# SCH_Embedded_Watch_2023-10-30.net
KiCad netlist of a schematic drawn in EasyEDA
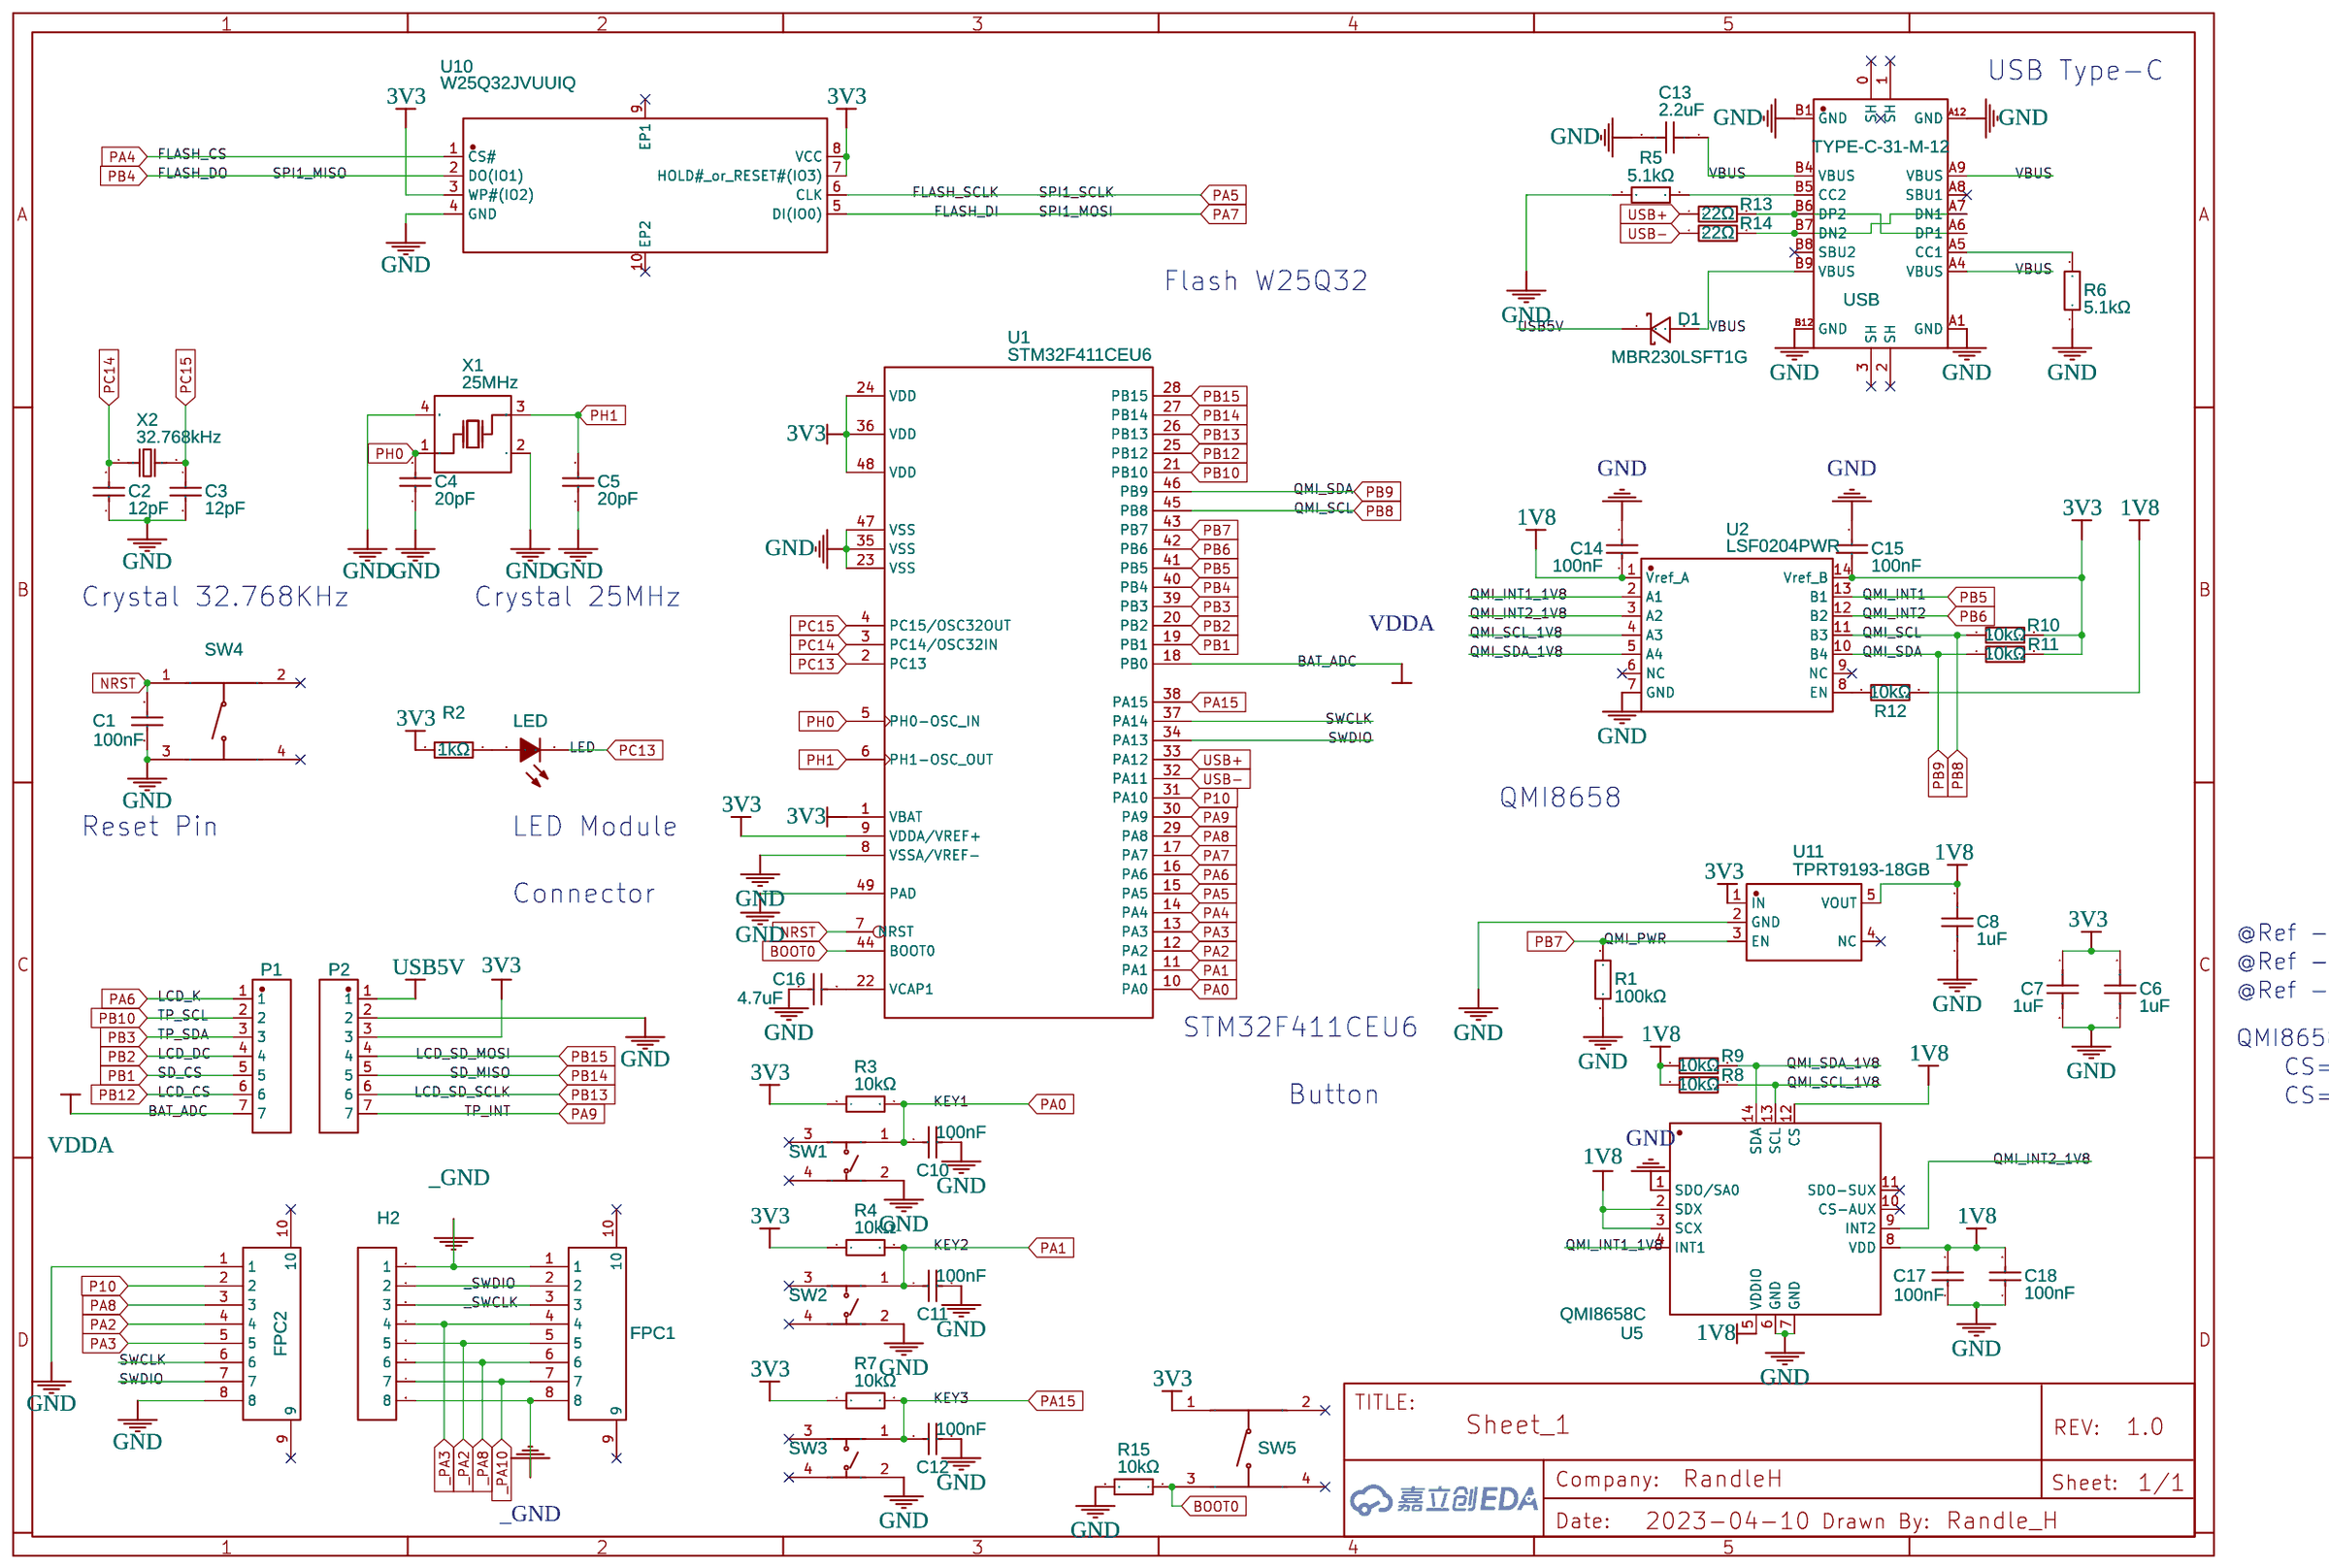
[diagram p0: schematic sheet]

(export (version "E")
  (design (tool "Eeschema 10.0.6"))
  (components
    (comp (ref "C1")
      (value "100nF")
      (fields
        (field (name "Manufacturer Part") "CL05B104KO5NNNC")
        (field (name "Manufacturer") "SAMSUNG(三星)")
      )
      (libsource (lib "") (part "CL05B104KO5NNNC"))
    )
    (comp (ref "C2")
      (value "12pF")
      (fields (field (name "Manufacturer Part") "0402CG120J500NT") (field (name "Manufacturer") "FH(风华)"))
      (libsource (lib "") (part "0402CG120J500NT_1"))
    )
    (comp (ref "C3")
      (value "12pF")
      (fields (field (name "Manufacturer Part") "0402CG120J500NT") (field (name "Manufacturer") "FH(风华)"))
      (libsource (lib "") (part "0402CG120J500NT"))
    )
    (comp (ref "C4")
      (value "20pF")
      (fields (field (name "Manufacturer Part") "0402CG200J500NT") (field (name "Manufacturer") "FH(风华)"))
      (libsource (lib "") (part "0402CG200J500NT"))
    )
    (comp (ref "C5")
      (value "20pF")
      (fields (field (name "Manufacturer Part") "0402CG200J500NT") (field (name "Manufacturer") "FH(风华)"))
      (libsource (lib "") (part "0402CG200J500NT"))
    )
    (comp (ref "C6")
      (value "1uF")
      (fields
        (field (name "Manufacturer Part") "CL05A105KA5NQNC")
        (field (name "Manufacturer") "SAMSUNG(三星)")
      )
      (libsource (lib "") (part "CL05A105KA5NQNC"))
    )
    (comp (ref "C7")
      (value "1uF")
      (fields
        (field (name "Manufacturer Part") "CL05A105KA5NQNC")
        (field (name "Manufacturer") "SAMSUNG(三星)")
      )
      (libsource (lib "") (part "CL05A105KA5NQNC_1"))
    )
    (comp (ref "C8")
      (value "1uF")
      (fields
        (field (name "Manufacturer Part") "CL05A105KA5NQNC")
        (field (name "Manufacturer") "SAMSUNG(三星)")
      )
      (libsource (lib "") (part "CL05A105KA5NQNC"))
    )
    (comp (ref "C10")
      (value "100nF")
      (fields
        (field (name "Manufacturer Part") "CL05B104KO5NNNC")
        (field (name "Manufacturer") "SAMSUNG(三星)")
      )
      (libsource (lib "") (part "CL05B104KO5NNNC_2"))
    )
    (comp (ref "C11")
      (value "100nF")
      (fields
        (field (name "Manufacturer Part") "CL05B104KO5NNNC")
        (field (name "Manufacturer") "SAMSUNG(三星)")
      )
      (libsource (lib "") (part "CL05B104KO5NNNC_2"))
    )
    (comp (ref "C12")
      (value "100nF")
      (fields
        (field (name "Manufacturer Part") "CL05B104KO5NNNC")
        (field (name "Manufacturer") "SAMSUNG(三星)")
      )
      (libsource (lib "") (part "CL05B104KO5NNNC_2"))
    )
    (comp (ref "C13")
      (value "2.2uF")
      (fields
        (field (name "Manufacturer Part") "CL21A225KBQNNNE")
        (field (name "Manufacturer") "SAMSUNG(三星)")
      )
      (libsource (lib "") (part "CL21A225KBQNNNE"))
    )
    (comp (ref "C14")
      (value "100nF")
      (fields
        (field (name "Manufacturer Part") "CL05B104KO5NNNC")
        (field (name "Manufacturer") "SAMSUNG(三星)")
      )
      (libsource (lib "") (part "CL05B104KO5NNNC_3"))
    )
    (comp (ref "C15")
      (value "100nF")
      (fields
        (field (name "Manufacturer Part") "CL05B104KO5NNNC")
        (field (name "Manufacturer") "SAMSUNG(三星)")
      )
      (libsource (lib "") (part "CL05B104KO5NNNC_1"))
    )
    (comp (ref "C16")
      (value "4.7uF")
      (fields
        (field (name "Manufacturer Part") "CL05A475MP5NRNC")
        (field (name "Manufacturer") "SAMSUNG(三星)")
      )
      (libsource (lib "") (part "CL05A475MP5NRNC"))
    )
    (comp (ref "C17")
      (value "100nF")
      (fields
        (field (name "Manufacturer Part") "CL05B104KO5NNNC")
        (field (name "Manufacturer") "SAMSUNG(三星)")
      )
      (libsource (lib "") (part "CL05B104KO5NNNC"))
    )
    (comp (ref "C18")
      (value "100nF")
      (fields
        (field (name "Manufacturer Part") "CL05B104KO5NNNC")
        (field (name "Manufacturer") "SAMSUNG(三星)")
      )
      (libsource (lib "") (part "CL05B104KO5NNNC_1"))
    )
    (comp (ref "D1")
      (value "MBR230LSFT1G")
      (fields (field (name "Manufacturer") "onsemi(安森美)"))
      (libsource (lib "") (part "MBR230LSFT1G"))
    )
    (comp (ref "FPC1")
      (value "C2883764")
      (fields (field (name "Manufacturer Part") "AFC01-S08FCA-00") (field (name "Manufacturer") "JS(钜硕电子)"))
      (libsource (lib "") (part "AFC01-S08FCA-00"))
    )
    (comp (ref "FPC2")
      (value "C2883764")
      (fields (field (name "Manufacturer Part") "AFC01-S08FCA-00") (field (name "Manufacturer") "JS(钜硕电子)"))
      (libsource (lib "") (part "AFC01-S08FCA-00"))
    )
    (comp (ref "H2") (value "HDR-F-2.54_1x8") (libsource (lib "") (part "HDR-F-2.54_1x8")))
    (comp (ref "LED")
      (value "19-213/Y2C-CQ2R2L/3T(CY)")
      (fields (field (name "Manufacturer") "EVERLIGHT(亿光)"))
      (libsource (lib "") (part "19-213/Y2C-CQ2R2L/3T(CY)"))
    )
    (comp (ref "P1")
      (value "PM2.54-1*7")
      (fields
        (field (name "Manufacturer Part") "X6511WVS-07H-C60D48R1")
        (field (name "Manufacturer") "XKB Connectivity(中国星坤)")
      )
      (libsource (lib "") (part "PM2.54-1*7_1"))
    )
    (comp (ref "P2")
      (value "PM2.54-1*7")
      (fields
        (field (name "Manufacturer Part") "X6511WVS-07H-C60D48R1")
        (field (name "Manufacturer") "XKB Connectivity(中国星坤)")
      )
      (libsource (lib "") (part "PM2.54-1*7"))
    )
    (comp (ref "R1")
      (value "100kΩ")
      (fields
        (field (name "Manufacturer Part") "0402WGF1003TCE")
        (field (name "Manufacturer") "UNI-ROYAL(厚声)")
      )
      (libsource (lib "") (part "0402WGF1003TCE"))
    )
    (comp (ref "R2")
      (value "1kΩ")
      (fields
        (field (name "Manufacturer Part") "0402WGF1001TCE")
        (field (name "Manufacturer") "UNI-ROYAL(厚声)")
      )
      (libsource (lib "") (part "0402WGF1001TCE"))
    )
    (comp (ref "R3")
      (value "10kΩ")
      (fields
        (field (name "Manufacturer Part") "0402WGF1002TCE")
        (field (name "Manufacturer") "UNI-ROYAL(厚声)")
      )
      (libsource (lib "") (part "0402WGF1002TCE"))
    )
    (comp (ref "R4")
      (value "10kΩ")
      (fields
        (field (name "Manufacturer Part") "0402WGF1002TCE")
        (field (name "Manufacturer") "UNI-ROYAL(厚声)")
      )
      (libsource (lib "") (part "0402WGF1002TCE"))
    )
    (comp (ref "R5")
      (value "5.1kΩ")
      (fields
        (field (name "Manufacturer Part") "0402WGF5101TCE")
        (field (name "Manufacturer") "UNI-ROYAL(厚声)")
      )
      (libsource (lib "") (part "0402WGF5101TCE_1"))
    )
    (comp (ref "R6")
      (value "5.1kΩ")
      (fields
        (field (name "Manufacturer Part") "0402WGF5101TCE")
        (field (name "Manufacturer") "UNI-ROYAL(厚声)")
      )
      (libsource (lib "") (part "0402WGF5101TCE"))
    )
    (comp (ref "R7")
      (value "10kΩ")
      (fields
        (field (name "Manufacturer Part") "0402WGF1002TCE")
        (field (name "Manufacturer") "UNI-ROYAL(厚声)")
      )
      (libsource (lib "") (part "0402WGF1002TCE"))
    )
    (comp (ref "R8")
      (value "10kΩ")
      (fields
        (field (name "Manufacturer Part") "0402WGF1002TCE")
        (field (name "Manufacturer") "UNI-ROYAL(厚声)")
      )
      (libsource (lib "") (part "0402WGF1002TCE"))
    )
    (comp (ref "R9")
      (value "10kΩ")
      (fields
        (field (name "Manufacturer Part") "0402WGF1002TCE")
        (field (name "Manufacturer") "UNI-ROYAL(厚声)")
      )
      (libsource (lib "") (part "0402WGF1002TCE"))
    )
    (comp (ref "R10")
      (value "10kΩ")
      (fields
        (field (name "Manufacturer Part") "0402WGF1002TCE")
        (field (name "Manufacturer") "UNI-ROYAL(厚声)")
      )
      (libsource (lib "") (part "0402WGF1002TCE"))
    )
    (comp (ref "R11")
      (value "10kΩ")
      (fields
        (field (name "Manufacturer Part") "0402WGF1002TCE")
        (field (name "Manufacturer") "UNI-ROYAL(厚声)")
      )
      (libsource (lib "") (part "0402WGF1002TCE"))
    )
    (comp (ref "R12")
      (value "10kΩ")
      (fields
        (field (name "Manufacturer Part") "0402WGF1002TCE")
        (field (name "Manufacturer") "UNI-ROYAL(厚声)")
      )
      (libsource (lib "") (part "0402WGF1002TCE"))
    )
    (comp (ref "R13")
      (value "22Ω")
      (fields
        (field (name "Manufacturer Part") "0402WGF220JTCE")
        (field (name "Manufacturer") "UNI-ROYAL(厚声)")
      )
      (libsource (lib "") (part "0402WGF220JTCE"))
    )
    (comp (ref "R14")
      (value "22Ω")
      (fields
        (field (name "Manufacturer Part") "0402WGF220JTCE")
        (field (name "Manufacturer") "UNI-ROYAL(厚声)")
      )
      (libsource (lib "") (part "0402WGF220JTCE"))
    )
    (comp (ref "R15")
      (value "10kΩ")
      (fields
        (field (name "Manufacturer Part") "0402WGF1002TCE")
        (field (name "Manufacturer") "UNI-ROYAL(厚声)")
      )
      (libsource (lib "") (part "0402WGF1002TCE_1"))
    )
    (comp (ref "SW1")
      (value "EVQPUD02K")
      (fields (field (name "Manufacturer") "PANASONIC(松下)"))
      (libsource (lib "") (part "EVQPUD02K"))
    )
    (comp (ref "SW2")
      (value "EVQPUD02K")
      (fields (field (name "Manufacturer") "PANASONIC(松下)"))
      (libsource (lib "") (part "EVQPUD02K"))
    )
    (comp (ref "SW3")
      (value "EVQPUD02K")
      (fields (field (name "Manufacturer") "PANASONIC(松下)"))
      (libsource (lib "") (part "EVQPUD02K"))
    )
    (comp (ref "SW4")
      (value "PTS830GM140SMTRLFS")
      (fields (field (name "Manufacturer") "C&K"))
      (libsource (lib "") (part "PTS830GM140SMTRLFS"))
    )
    (comp (ref "SW5")
      (value "PTS830GM140SMTRLFS")
      (fields (field (name "Manufacturer") "C&K"))
      (libsource (lib "") (part "PTS830GM140SMTRLFS"))
    )
    (comp (ref "U1")
      (value "STM32F411CEU6")
      (fields (field (name "Manufacturer") "ST(意法半导体)"))
      (libsource (lib "") (part "STM32F411CEU6"))
    )
    (comp (ref "U2")
      (value "LSF0204PWR")
      (fields (field (name "Manufacturer") "TI(德州仪器)"))
      (libsource (lib "") (part "LSF0204PWR"))
    )
    (comp (ref "U5")
      (value "QMI8658C")
      (fields (field (name "Manufacturer") "QST(上海矽睿)"))
      (libsource (lib "") (part "QMI8658C"))
    )
    (comp (ref "U10")
      (value "W25Q32JVUUIQ")
      (fields (field (name "Manufacturer") "WINBOND(华邦)"))
      (libsource (lib "") (part "W25Q32JVUUIQ"))
    )
    (comp (ref "U11")
      (value "TPRT9193-18GB")
      (fields (field (name "Manufacturer") "TECH PUBLIC(台舟)"))
      (libsource (lib "") (part "TPRT9193-18GB"))
    )
    (comp (ref "USB")
      (value "TYPE-C-31-M-12")
      (fields (field (name "Manufacturer") "韩国韩荣"))
      (libsource (lib "") (part "TYPE-C-31-M-12"))
    )
    (comp (ref "X1")
      (value "25MHz")
      (fields (field (name "Manufacturer Part") "TAXM25M4RLBCCT2T") (field (name "Manufacturer") "TAE(雅晶鑫)"))
      (libsource (lib "") (part "SMD-3225_4P25MHZ20PF10PPM-40&#126;+85℃"))
    )
    (comp (ref "X2")
      (value "32.768kHz")
      (fields (field (name "Manufacturer Part") "Q13FC1350000400") (field (name "Manufacturer") "EPSON(爱普生)"))
      (libsource (lib "") (part "Q13FC1350000400"))
    )
  )
  (nets
    (net (code "1") (name "/QMI_INT1_1V8") (class "Default")
      (node (ref "U2") (pin "2") (pinfunction "A1_2") (pintype "unspecified"))
      (node (ref "U5") (pin "4") (pinfunction "INT1_4") (pintype "unspecified"))
    )
    (net (code "2") (name "/QMI_INT2_1V8") (class "Default")
      (node (ref "U2") (pin "3") (pinfunction "A2_3") (pintype "unspecified"))
      (node (ref "U5") (pin "9") (pinfunction "INT2_9") (pintype "unspecified"))
    )
    (net (code "3") (name "/QMI_SCL_1V8") (class "Default")
      (node (ref "R8") (pin "2") (pinfunction "2_2") (pintype "input"))
      (node (ref "U2") (pin "4") (pinfunction "A3_4") (pintype "unspecified"))
      (node (ref "U5") (pin "13") (pinfunction "SCL_13") (pintype "unspecified"))
    )
    (net (code "4") (name "/QMI_SDA_1V8") (class "Default")
      (node (ref "R9") (pin "2") (pinfunction "2_2") (pintype "input"))
      (node (ref "U2") (pin "5") (pinfunction "A4_5") (pintype "unspecified"))
      (node (ref "U5") (pin "14") (pinfunction "SDA_14") (pintype "unspecified"))
    )
    (net (code "5") (name "/SWCLK") (class "Default")
      (node (ref "FPC2") (pin "6") (pinfunction "6_6") (pintype "unspecified"))
      (node (ref "U1") (pin "37") (pinfunction "PA14_37") (pintype "unspecified"))
    )
    (net (code "6") (name "/SWDIO") (class "Default")
      (node (ref "FPC2") (pin "7") (pinfunction "7_7") (pintype "unspecified"))
      (node (ref "U1") (pin "34") (pinfunction "PA13_34") (pintype "unspecified"))
    )
    (net (code "7") (name "/VBUS") (class "Default")
      (node (ref "C13") (pin "1") (pinfunction "1_1") (pintype "unspecified"))
      (node (ref "D1") (pin "2") (pinfunction "A_2") (pintype "unspecified"))
      (node (ref "USB") (pin "A4") (pinfunction "VBUS_A4") (pintype "unspecified"))
      (node (ref "USB") (pin "A9") (pinfunction "VBUS_A9") (pintype "unspecified"))
      (node (ref "USB") (pin "B4") (pinfunction "VBUS_B4") (pintype "unspecified"))
      (node (ref "USB") (pin "B9") (pinfunction "VBUS_B9") (pintype "unspecified"))
    )
    (net (code "8") (name "/_SWCLK") (class "Default")
      (node (ref "FPC1") (pin "3") (pinfunction "3_3") (pintype "unspecified"))
      (node (ref "H2") (pin "3") (pinfunction "3_3") (pintype "unspecified"))
    )
    (net (code "9") (name "/_SWDIO") (class "Default")
      (node (ref "FPC1") (pin "2") (pinfunction "2_2") (pintype "unspecified"))
      (node (ref "H2") (pin "2") (pinfunction "2_2") (pintype "unspecified"))
    )
    (net (code "10") (name "1V8") (class "Default")
      (node (ref "C14") (pin "1") (pinfunction "1_1") (pintype "input"))
      (node (ref "C17") (pin "1") (pinfunction "1_1") (pintype "input"))
      (node (ref "C18") (pin "2") (pinfunction "2_2") (pintype "input"))
      (node (ref "C8") (pin "2") (pinfunction "2_2") (pintype "unspecified"))
      (node (ref "R12") (pin "2") (pinfunction "2_2") (pintype "input"))
      (node (ref "R8") (pin "1") (pinfunction "1_1") (pintype "input"))
      (node (ref "R9") (pin "1") (pinfunction "1_1") (pintype "input"))
      (node (ref "U11") (pin "5") (pinfunction "VOUT_5") (pintype "unspecified"))
      (node (ref "U2") (pin "1") (pinfunction "Vref_A_1") (pintype "unspecified"))
      (node (ref "U5") (pin "12") (pinfunction "CS_12") (pintype "unspecified"))
      (node (ref "U5") (pin "2") (pinfunction "SDX_2") (pintype "unspecified"))
      (node (ref "U5") (pin "3") (pinfunction "SCX_3") (pintype "unspecified"))
      (node (ref "U5") (pin "5") (pinfunction "VDDIO_5") (pintype "unspecified"))
      (node (ref "U5") (pin "8") (pinfunction "VDD_8") (pintype "unspecified"))
    )
    (net (code "11") (name "3V3") (class "Default")
      (node (ref "C15") (pin "1") (pinfunction "1_1") (pintype "input"))
      (node (ref "C6") (pin "2") (pinfunction "2_2") (pintype "unspecified"))
      (node (ref "C7") (pin "1") (pinfunction "1_1") (pintype "unspecified"))
      (node (ref "P2") (pin "3") (pinfunction "3_3") (pintype "unspecified"))
      (node (ref "R10") (pin "2") (pinfunction "2_2") (pintype "input"))
      (node (ref "R11") (pin "2") (pinfunction "2_2") (pintype "input"))
      (node (ref "R2") (pin "1") (pinfunction "1_1") (pintype "input"))
      (node (ref "R3") (pin "1") (pinfunction "1_1") (pintype "input"))
      (node (ref "R4") (pin "1") (pinfunction "1_1") (pintype "input"))
      (node (ref "R7") (pin "1") (pinfunction "1_1") (pintype "input"))
      (node (ref "SW5") (pin "1") (pinfunction "1_1") (pintype "unspecified"))
      (node (ref "U1") (pin "1") (pinfunction "VBAT_1") (pintype "passive"))
      (node (ref "U1") (pin "24") (pinfunction "VDD_24") (pintype "unspecified"))
      (node (ref "U1") (pin "36") (pinfunction "VDD_36") (pintype "unspecified"))
      (node (ref "U1") (pin "48") (pinfunction "VDD_48") (pintype "unspecified"))
      (node (ref "U1") (pin "9") (pinfunction "VDDA/VREF+_9") (pintype "passive"))
      (node (ref "U10") (pin "3") (pinfunction "WP#(IO2)_3") (pintype "unspecified"))
      (node (ref "U10") (pin "7") (pinfunction "HOLD#_or_RESET#(IO3)_7") (pintype "unspecified"))
      (node (ref "U10") (pin "8") (pinfunction "VCC_8") (pintype "unspecified"))
      (node (ref "U11") (pin "1") (pinfunction "IN_1") (pintype "unspecified"))
      (node (ref "U2") (pin "14") (pinfunction "Vref_B_14") (pintype "unspecified"))
    )
    (net (code "12") (name "BOOT0") (class "Default")
      (node (ref "R15") (pin "1") (pinfunction "1_1") (pintype "input"))
      (node (ref "SW5") (pin "3") (pinfunction "3_3") (pintype "unspecified"))
      (node (ref "U1") (pin "44") (pinfunction "BOOT0_44") (pintype "input"))
    )
    (net (code "13") (name "GND") (class "Default")
      (node (ref "C1") (pin "2") (pinfunction "2_2") (pintype "input"))
      (node (ref "C10") (pin "2") (pinfunction "2_2") (pintype "input"))
      (node (ref "C11") (pin "2") (pinfunction "2_2") (pintype "input"))
      (node (ref "C12") (pin "2") (pinfunction "2_2") (pintype "input"))
      (node (ref "C13") (pin "2") (pinfunction "2_2") (pintype "unspecified"))
      (node (ref "C14") (pin "2") (pinfunction "2_2") (pintype "input"))
      (node (ref "C15") (pin "2") (pinfunction "2_2") (pintype "input"))
      (node (ref "C16") (pin "1") (pinfunction "1_1") (pintype "input"))
      (node (ref "C17") (pin "2") (pinfunction "2_2") (pintype "input"))
      (node (ref "C18") (pin "1") (pinfunction "1_1") (pintype "input"))
      (node (ref "C2") (pin "1") (pinfunction "1_1") (pintype "input"))
      (node (ref "C3") (pin "2") (pinfunction "2_2") (pintype "input"))
      (node (ref "C4") (pin "1") (pinfunction "1_1") (pintype "input"))
      (node (ref "C5") (pin "1") (pinfunction "1_1") (pintype "input"))
      (node (ref "C6") (pin "1") (pinfunction "1_1") (pintype "unspecified"))
      (node (ref "C7") (pin "2") (pinfunction "2_2") (pintype "unspecified"))
      (node (ref "C8") (pin "1") (pinfunction "1_1") (pintype "unspecified"))
      (node (ref "FPC2") (pin "1") (pinfunction "1_1") (pintype "unspecified"))
      (node (ref "FPC2") (pin "8") (pinfunction "8_8") (pintype "unspecified"))
      (node (ref "P2") (pin "2") (pinfunction "2_2") (pintype "unspecified"))
      (node (ref "R1") (pin "1") (pinfunction "1_1") (pintype "input"))
      (node (ref "R15") (pin "2") (pinfunction "2_2") (pintype "input"))
      (node (ref "R5") (pin "2") (pinfunction "2_2") (pintype "input"))
      (node (ref "R6") (pin "1") (pinfunction "1_1") (pintype "input"))
      (node (ref "SW1") (pin "2") (pinfunction "2_2") (pintype "unspecified"))
      (node (ref "SW2") (pin "2") (pinfunction "2_2") (pintype "unspecified"))
      (node (ref "SW3") (pin "2") (pinfunction "2_2") (pintype "unspecified"))
      (node (ref "SW4") (pin "3") (pinfunction "3_3") (pintype "unspecified"))
      (node (ref "U1") (pin "23") (pinfunction "VSS_23") (pintype "unspecified"))
      (node (ref "U1") (pin "35") (pinfunction "VSS_35") (pintype "unspecified"))
      (node (ref "U1") (pin "47") (pinfunction "VSS_47") (pintype "unspecified"))
      (node (ref "U1") (pin "49") (pinfunction "PAD_49") (pintype "passive"))
      (node (ref "U1") (pin "8") (pinfunction "VSSA/VREF-_8") (pintype "passive"))
      (node (ref "U10") (pin "4") (pinfunction "GND_4") (pintype "unspecified"))
      (node (ref "U11") (pin "2") (pinfunction "GND_2") (pintype "unspecified"))
      (node (ref "U2") (pin "7") (pinfunction "GND_7") (pintype "unspecified"))
      (node (ref "U5") (pin "1") (pinfunction "SDO/SA0_1") (pintype "unspecified"))
      (node (ref "U5") (pin "6") (pinfunction "GND_6") (pintype "unspecified"))
      (node (ref "U5") (pin "7") (pinfunction "GND_7") (pintype "unspecified"))
      (node (ref "USB") (pin "A1") (pinfunction "GND_A1") (pintype "unspecified"))
      (node (ref "USB") (pin "A12") (pinfunction "GND_A12") (pintype "unspecified"))
      (node (ref "USB") (pin "B1") (pinfunction "GND_B1") (pintype "unspecified"))
      (node (ref "USB") (pin "B12") (pinfunction "GND_B12") (pintype "unspecified"))
      (node (ref "X1") (pin "2") (pinfunction "GND_2") (pintype "unspecified"))
      (node (ref "X1") (pin "4") (pinfunction "GND_4") (pintype "unspecified"))
    )
    (net (code "14") (name "NRST") (class "Default")
      (node (ref "C1") (pin "1") (pinfunction "1_1") (pintype "input"))
      (node (ref "SW4") (pin "1") (pinfunction "1_1") (pintype "unspecified"))
      (node (ref "U1") (pin "7") (pinfunction "NRST_7") (pintype "unspecified"))
    )
    (net (code "15") (name "Net-(LED-A)") (class "Default")
      (node (ref "LED") (pin "2") (pinfunction "A_2") (pintype "input"))
      (node (ref "R2") (pin "2") (pinfunction "2_2") (pintype "input"))
    )
    (net (code "16") (name "Net-(U1-VCAP1)") (class "Default")
      (node (ref "C16") (pin "2") (pinfunction "2_2") (pintype "input"))
      (node (ref "U1") (pin "22") (pinfunction "VCAP1_22") (pintype "passive"))
    )
    (net (code "17") (name "Net-(U2-EN)") (class "Default")
      (node (ref "R12") (pin "1") (pinfunction "1_1") (pintype "input"))
      (node (ref "U2") (pin "8") (pinfunction "EN_8") (pintype "unspecified"))
    )
    (net (code "18") (name "Net-(USB-CC1)") (class "Default")
      (node (ref "R6") (pin "2") (pinfunction "2_2") (pintype "input"))
      (node (ref "USB") (pin "A5") (pinfunction "CC1_A5") (pintype "unspecified"))
    )
    (net (code "19") (name "Net-(USB-CC2)") (class "Default")
      (node (ref "R5") (pin "1") (pinfunction "1_1") (pintype "input"))
      (node (ref "USB") (pin "B5") (pinfunction "CC2_B5") (pintype "unspecified"))
    )
    (net (code "20") (name "Net-(USB-DN1)") (class "Default")
      (node (ref "R14") (pin "2") (pinfunction "2_2") (pintype "input"))
      (node (ref "USB") (pin "A7") (pinfunction "DN1_A7") (pintype "unspecified"))
      (node (ref "USB") (pin "B7") (pinfunction "DN2_B7") (pintype "unspecified"))
    )
    (net (code "21") (name "Net-(USB-DP1)") (class "Default")
      (node (ref "R13") (pin "2") (pinfunction "2_2") (pintype "input"))
      (node (ref "USB") (pin "A6") (pinfunction "DP1_A6") (pintype "unspecified"))
      (node (ref "USB") (pin "B6") (pinfunction "DP2_B6") (pintype "unspecified"))
    )
    (net (code "22") (name "P10") (class "Default")
      (node (ref "FPC2") (pin "2") (pinfunction "2_2") (pintype "unspecified"))
      (node (ref "U1") (pin "31") (pinfunction "PA10_31") (pintype "unspecified"))
    )
    (net (code "23") (name "PA0") (class "Default")
      (node (ref "C10") (pin "1") (pinfunction "1_1") (pintype "input"))
      (node (ref "R3") (pin "2") (pinfunction "2_2") (pintype "input"))
      (node (ref "SW1") (pin "1") (pinfunction "1_1") (pintype "unspecified"))
      (node (ref "U1") (pin "10") (pinfunction "PA0_10") (pintype "unspecified"))
    )
    (net (code "24") (name "PA1") (class "Default")
      (node (ref "C11") (pin "1") (pinfunction "1_1") (pintype "input"))
      (node (ref "R4") (pin "2") (pinfunction "2_2") (pintype "input"))
      (node (ref "SW2") (pin "1") (pinfunction "1_1") (pintype "unspecified"))
      (node (ref "U1") (pin "11") (pinfunction "PA1_11") (pintype "unspecified"))
    )
    (net (code "25") (name "PA2") (class "Default")
      (node (ref "FPC2") (pin "4") (pinfunction "4_4") (pintype "unspecified"))
      (node (ref "U1") (pin "12") (pinfunction "PA2_12") (pintype "unspecified"))
    )
    (net (code "26") (name "PA3") (class "Default")
      (node (ref "FPC2") (pin "5") (pinfunction "5_5") (pintype "unspecified"))
      (node (ref "U1") (pin "13") (pinfunction "PA3_13") (pintype "unspecified"))
    )
    (net (code "27") (name "PA4") (class "Default")
      (node (ref "U1") (pin "14") (pinfunction "PA4_14") (pintype "unspecified"))
      (node (ref "U10") (pin "1") (pinfunction "CS#_1") (pintype "unspecified"))
    )
    (net (code "28") (name "PA5") (class "Default")
      (node (ref "U1") (pin "15") (pinfunction "PA5_15") (pintype "unspecified"))
      (node (ref "U10") (pin "6") (pinfunction "CLK_6") (pintype "unspecified"))
    )
    (net (code "29") (name "PA6") (class "Default")
      (node (ref "P1") (pin "1") (pinfunction "1_1") (pintype "unspecified"))
      (node (ref "U1") (pin "16") (pinfunction "PA6_16") (pintype "unspecified"))
    )
    (net (code "30") (name "PA7") (class "Default")
      (node (ref "U1") (pin "17") (pinfunction "PA7_17") (pintype "unspecified"))
      (node (ref "U10") (pin "5") (pinfunction "DI(IO0)_5") (pintype "unspecified"))
    )
    (net (code "31") (name "PA8") (class "Default")
      (node (ref "FPC2") (pin "3") (pinfunction "3_3") (pintype "unspecified"))
      (node (ref "U1") (pin "29") (pinfunction "PA8_29") (pintype "unspecified"))
    )
    (net (code "32") (name "PA9") (class "Default")
      (node (ref "P2") (pin "7") (pinfunction "7_7") (pintype "unspecified"))
      (node (ref "U1") (pin "30") (pinfunction "PA9_30") (pintype "unspecified"))
    )
    (net (code "33") (name "PA15") (class "Default")
      (node (ref "C12") (pin "1") (pinfunction "1_1") (pintype "input"))
      (node (ref "R7") (pin "2") (pinfunction "2_2") (pintype "input"))
      (node (ref "SW3") (pin "1") (pinfunction "1_1") (pintype "unspecified"))
      (node (ref "U1") (pin "38") (pinfunction "PA15_38") (pintype "unspecified"))
    )
    (net (code "34") (name "PB1") (class "Default")
      (node (ref "P1") (pin "5") (pinfunction "5_5") (pintype "unspecified"))
      (node (ref "U1") (pin "19") (pinfunction "PB1_19") (pintype "unspecified"))
    )
    (net (code "35") (name "PB2") (class "Default")
      (node (ref "P1") (pin "4") (pinfunction "4_4") (pintype "unspecified"))
      (node (ref "U1") (pin "20") (pinfunction "PB2_20") (pintype "unspecified"))
    )
    (net (code "36") (name "PB3") (class "Default")
      (node (ref "P1") (pin "3") (pinfunction "3_3") (pintype "unspecified"))
      (node (ref "U1") (pin "39") (pinfunction "PB3_39") (pintype "unspecified"))
    )
    (net (code "37") (name "PB4") (class "Default")
      (node (ref "U1") (pin "40") (pinfunction "PB4_40") (pintype "unspecified"))
      (node (ref "U10") (pin "2") (pinfunction "DO(IO1)_2") (pintype "unspecified"))
    )
    (net (code "38") (name "PB5") (class "Default")
      (node (ref "U1") (pin "41") (pinfunction "PB5_41") (pintype "unspecified"))
      (node (ref "U2") (pin "13") (pinfunction "B1_13") (pintype "unspecified"))
    )
    (net (code "39") (name "PB6") (class "Default")
      (node (ref "U1") (pin "42") (pinfunction "PB6_42") (pintype "unspecified"))
      (node (ref "U2") (pin "12") (pinfunction "B2_12") (pintype "unspecified"))
    )
    (net (code "40") (name "PB7") (class "Default")
      (node (ref "R1") (pin "2") (pinfunction "2_2") (pintype "input"))
      (node (ref "U1") (pin "43") (pinfunction "PB7_43") (pintype "unspecified"))
      (node (ref "U11") (pin "3") (pinfunction "EN_3") (pintype "unspecified"))
    )
    (net (code "41") (name "PB8") (class "Default")
      (node (ref "R10") (pin "1") (pinfunction "1_1") (pintype "input"))
      (node (ref "U1") (pin "45") (pinfunction "PB8_45") (pintype "unspecified"))
      (node (ref "U2") (pin "11") (pinfunction "B3_11") (pintype "unspecified"))
    )
    (net (code "42") (name "PB9") (class "Default")
      (node (ref "R11") (pin "1") (pinfunction "1_1") (pintype "input"))
      (node (ref "U1") (pin "46") (pinfunction "PB9_46") (pintype "unspecified"))
      (node (ref "U2") (pin "10") (pinfunction "B4_10") (pintype "unspecified"))
    )
    (net (code "43") (name "PB10") (class "Default")
      (node (ref "P1") (pin "2") (pinfunction "2_2") (pintype "unspecified"))
      (node (ref "U1") (pin "21") (pinfunction "PB10_21") (pintype "unspecified"))
    )
    (net (code "44") (name "PB12") (class "Default")
      (node (ref "P1") (pin "6") (pinfunction "6_6") (pintype "unspecified"))
      (node (ref "U1") (pin "25") (pinfunction "PB12_25") (pintype "unspecified"))
    )
    (net (code "45") (name "PB13") (class "Default")
      (node (ref "P2") (pin "6") (pinfunction "6_6") (pintype "unspecified"))
      (node (ref "U1") (pin "26") (pinfunction "PB13_26") (pintype "unspecified"))
    )
    (net (code "46") (name "PB14") (class "Default")
      (node (ref "P2") (pin "5") (pinfunction "5_5") (pintype "unspecified"))
      (node (ref "U1") (pin "27") (pinfunction "PB14_27") (pintype "unspecified"))
    )
    (net (code "47") (name "PB15") (class "Default")
      (node (ref "P2") (pin "4") (pinfunction "4_4") (pintype "unspecified"))
      (node (ref "U1") (pin "28") (pinfunction "PB15_28") (pintype "unspecified"))
    )
    (net (code "48") (name "PC13") (class "Default")
      (node (ref "LED") (pin "1") (pinfunction "C_1") (pintype "input"))
      (node (ref "U1") (pin "2") (pinfunction "PC13_2") (pintype "unspecified"))
    )
    (net (code "49") (name "PC14") (class "Default")
      (node (ref "C2") (pin "2") (pinfunction "2_2") (pintype "input"))
      (node (ref "U1") (pin "3") (pinfunction "PC14/OSC32IN_3") (pintype "unspecified"))
      (node (ref "X2") (pin "1") (pinfunction "1_1") (pintype "unspecified"))
    )
    (net (code "50") (name "PC15") (class "Default")
      (node (ref "C3") (pin "1") (pinfunction "1_1") (pintype "input"))
      (node (ref "U1") (pin "4") (pinfunction "PC15/OSC32OUT_4") (pintype "unspecified"))
      (node (ref "X2") (pin "2") (pinfunction "2_2") (pintype "unspecified"))
    )
    (net (code "51") (name "PH0") (class "Default")
      (node (ref "C4") (pin "2") (pinfunction "2_2") (pintype "input"))
      (node (ref "U1") (pin "5") (pinfunction "PH0-OSC_IN_5") (pintype "unspecified"))
      (node (ref "X1") (pin "1") (pinfunction "OSC1_1") (pintype "unspecified"))
    )
    (net (code "52") (name "PH1") (class "Default")
      (node (ref "C5") (pin "2") (pinfunction "2_2") (pintype "input"))
      (node (ref "U1") (pin "6") (pinfunction "PH1-OSC_OUT_6") (pintype "unspecified"))
      (node (ref "X1") (pin "3") (pinfunction "OSC2_3") (pintype "unspecified"))
    )
    (net (code "53") (name "USB+") (class "Default")
      (node (ref "R13") (pin "1") (pinfunction "1_1") (pintype "input"))
      (node (ref "U1") (pin "33") (pinfunction "PA12_33") (pintype "unspecified"))
    )
    (net (code "54") (name "USB-") (class "Default")
      (node (ref "R14") (pin "1") (pinfunction "1_1") (pintype "input"))
      (node (ref "U1") (pin "32") (pinfunction "PA11_32") (pintype "unspecified"))
    )
    (net (code "55") (name "USB5V") (class "Default")
      (node (ref "D1") (pin "1") (pinfunction "C_1") (pintype "unspecified"))
      (node (ref "P2") (pin "1") (pinfunction "1_1") (pintype "unspecified"))
    )
    (net (code "56") (name "VDDA") (class "Default")
      (node (ref "P1") (pin "7") (pinfunction "7_7") (pintype "unspecified"))
      (node (ref "U1") (pin "18") (pinfunction "PB0_18") (pintype "unspecified"))
    )
    (net (code "57") (name "_GND") (class "Default")
      (node (ref "FPC1") (pin "1") (pinfunction "1_1") (pintype "unspecified"))
      (node (ref "FPC1") (pin "8") (pinfunction "8_8") (pintype "unspecified"))
      (node (ref "H2") (pin "1") (pinfunction "1_1") (pintype "unspecified"))
      (node (ref "H2") (pin "8") (pinfunction "8_8") (pintype "unspecified"))
    )
    (net (code "58") (name "_PA2") (class "Default")
      (node (ref "FPC1") (pin "5") (pinfunction "5_5") (pintype "unspecified"))
      (node (ref "H2") (pin "5") (pinfunction "5_5") (pintype "unspecified"))
    )
    (net (code "59") (name "_PA3") (class "Default")
      (node (ref "FPC1") (pin "4") (pinfunction "4_4") (pintype "unspecified"))
      (node (ref "H2") (pin "4") (pinfunction "4_4") (pintype "unspecified"))
    )
    (net (code "60") (name "_PA8") (class "Default")
      (node (ref "FPC1") (pin "6") (pinfunction "6_6") (pintype "unspecified"))
      (node (ref "H2") (pin "6") (pinfunction "6_6") (pintype "unspecified"))
    )
    (net (code "61") (name "_PA10") (class "Default")
      (node (ref "FPC1") (pin "7") (pinfunction "7_7") (pintype "unspecified"))
      (node (ref "H2") (pin "7") (pinfunction "7_7") (pintype "unspecified"))
    )
    (net (code "62") (name "unconnected-(FPC1-Pad9)") (class "Default")
      (node (ref "FPC1") (pin "9") (pinfunction "9_9") (pintype "unspecified+no_connect"))
    )
    (net (code "63") (name "unconnected-(FPC1-Pad10)") (class "Default")
      (node (ref "FPC1") (pin "10") (pinfunction "10_10") (pintype "unspecified+no_connect"))
    )
    (net (code "64") (name "unconnected-(FPC2-Pad9)") (class "Default")
      (node (ref "FPC2") (pin "9") (pinfunction "9_9") (pintype "unspecified+no_connect"))
    )
    (net (code "65") (name "unconnected-(FPC2-Pad10)") (class "Default")
      (node (ref "FPC2") (pin "10") (pinfunction "10_10") (pintype "unspecified+no_connect"))
    )
    (net (code "66") (name "unconnected-(SW1-Pad3)") (class "Default")
      (node (ref "SW1") (pin "3") (pinfunction "3_3") (pintype "unspecified+no_connect"))
    )
    (net (code "67") (name "unconnected-(SW1-Pad4)") (class "Default")
      (node (ref "SW1") (pin "4") (pinfunction "4_4") (pintype "unspecified+no_connect"))
    )
    (net (code "68") (name "unconnected-(SW2-Pad3)") (class "Default")
      (node (ref "SW2") (pin "3") (pinfunction "3_3") (pintype "unspecified+no_connect"))
    )
    (net (code "69") (name "unconnected-(SW2-Pad4)") (class "Default")
      (node (ref "SW2") (pin "4") (pinfunction "4_4") (pintype "unspecified+no_connect"))
    )
    (net (code "70") (name "unconnected-(SW3-Pad3)") (class "Default")
      (node (ref "SW3") (pin "3") (pinfunction "3_3") (pintype "unspecified+no_connect"))
    )
    (net (code "71") (name "unconnected-(SW3-Pad4)") (class "Default")
      (node (ref "SW3") (pin "4") (pinfunction "4_4") (pintype "unspecified+no_connect"))
    )
    (net (code "72") (name "unconnected-(SW4-Pad2)") (class "Default")
      (node (ref "SW4") (pin "2") (pinfunction "2_2") (pintype "unspecified+no_connect"))
    )
    (net (code "73") (name "unconnected-(SW4-Pad4)") (class "Default")
      (node (ref "SW4") (pin "4") (pinfunction "4_4") (pintype "unspecified+no_connect"))
    )
    (net (code "74") (name "unconnected-(SW5-Pad2)") (class "Default")
      (node (ref "SW5") (pin "2") (pinfunction "2_2") (pintype "unspecified+no_connect"))
    )
    (net (code "75") (name "unconnected-(SW5-Pad4)") (class "Default")
      (node (ref "SW5") (pin "4") (pinfunction "4_4") (pintype "unspecified+no_connect"))
    )
    (net (code "76") (name "unconnected-(U2-NC-Pad6)") (class "Default")
      (node (ref "U2") (pin "6") (pinfunction "NC_6") (pintype "unspecified+no_connect"))
    )
    (net (code "77") (name "unconnected-(U2-NC-Pad9)") (class "Default")
      (node (ref "U2") (pin "9") (pinfunction "NC_9") (pintype "unspecified+no_connect"))
    )
    (net (code "78") (name "unconnected-(U5-CS-AUX-Pad10)") (class "Default")
      (node (ref "U5") (pin "10") (pinfunction "CS-AUX_10") (pintype "unspecified+no_connect"))
    )
    (net (code "79") (name "unconnected-(U5-SDO-SUX-Pad11)") (class "Default")
      (node (ref "U5") (pin "11") (pinfunction "SDO-SUX_11") (pintype "unspecified+no_connect"))
    )
    (net (code "80") (name "unconnected-(U10-EP1-Pad9)") (class "Default")
      (node (ref "U10") (pin "9") (pinfunction "EP1_9") (pintype "unspecified+no_connect"))
    )
    (net (code "81") (name "unconnected-(U10-EP2-Pad10)") (class "Default")
      (node (ref "U10") (pin "10") (pinfunction "EP2_10") (pintype "unspecified+no_connect"))
    )
    (net (code "82") (name "unconnected-(U11-NC-Pad4)") (class "Default")
      (node (ref "U11") (pin "4") (pinfunction "NC_4") (pintype "unspecified+no_connect"))
    )
    (net (code "83") (name "unconnected-(USB-SBU1-PadA8)") (class "Default")
      (node (ref "USB") (pin "A8") (pinfunction "SBU1_A8") (pintype "unspecified+no_connect"))
    )
    (net (code "84") (name "unconnected-(USB-SBU2-PadB8)") (class "Default")
      (node (ref "USB") (pin "B8") (pinfunction "SBU2_B8") (pintype "unspecified+no_connect"))
    )
    (net (code "85") (name "unconnected-(USB-SH-Pad0)") (class "Default")
      (node (ref "USB") (pin "0") (pinfunction "SH_0") (pintype "unspecified+no_connect"))
    )
    (net (code "86") (name "unconnected-(USB-SH-Pad1)") (class "Default")
      (node (ref "USB") (pin "1") (pinfunction "SH_1") (pintype "unspecified+no_connect"))
    )
    (net (code "87") (name "unconnected-(USB-SH-Pad2)") (class "Default")
      (node (ref "USB") (pin "2") (pinfunction "SH_2") (pintype "unspecified+no_connect"))
    )
    (net (code "88") (name "unconnected-(USB-SH-Pad3)") (class "Default")
      (node (ref "USB") (pin "3") (pinfunction "SH_3") (pintype "unspecified+no_connect"))
    )
  )
)
